# SignalConditioning.net
KiCad netlist of a schematic drawn in Altium Designer
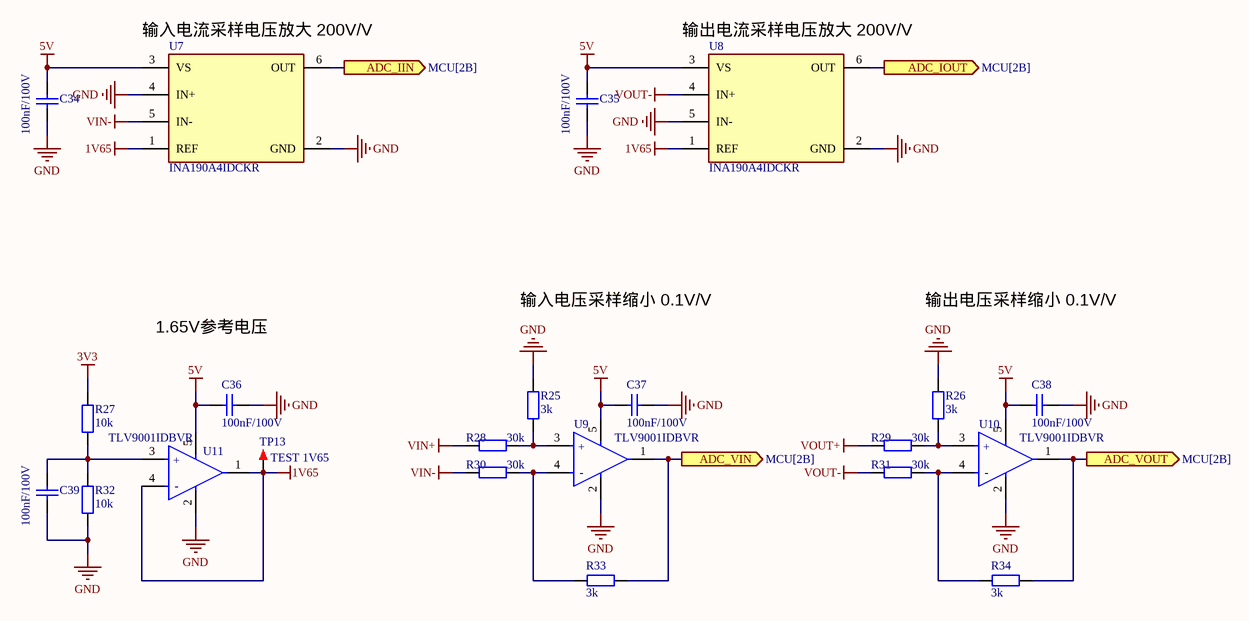
[diagram p0: SignalConditioning.SchDoc]

(export (version "E")
  (design (tool "Eeschema 10.0.6"))
  (components
    (comp (ref "C34")
      (value "100nF/100V")
      (footprint "C0402_L")
      (description "贴片电容")
      (libsource (lib "0.1 - 电阻-电容-电感-晶振-晶体-磁珠-电位器") (part "C"))
    )
    (comp (ref "C35")
      (value "100nF/100V")
      (footprint "C0402_L")
      (description "贴片电容")
      (libsource (lib "0.1 - 电阻-电容-电感-晶振-晶体-磁珠-电位器") (part "C"))
    )
    (comp (ref "C36")
      (value "100nF/100V")
      (footprint "C0402_L")
      (description "贴片电容")
      (libsource (lib "0.1 - 电阻-电容-电感-晶振-晶体-磁珠-电位器") (part "C"))
    )
    (comp (ref "C37")
      (value "100nF/100V")
      (footprint "C0402_L")
      (description "贴片电容")
      (libsource (lib "0.1 - 电阻-电容-电感-晶振-晶体-磁珠-电位器") (part "C"))
    )
    (comp (ref "C38")
      (value "100nF/100V")
      (footprint "C0402_L")
      (description "贴片电容")
      (libsource (lib "0.1 - 电阻-电容-电感-晶振-晶体-磁珠-电位器") (part "C"))
    )
    (comp (ref "C39")
      (value "100nF/100V")
      (footprint "C0402_L")
      (description "贴片电容")
      (libsource (lib "0.1 - 电阻-电容-电感-晶振-晶体-磁珠-电位器") (part "C"))
    )
    (comp (ref "R25")
      (value "3k")
      (footprint "R 0402_L")
      (description "贴片电阻")
      (fields (field (name "版权归属") "源创客"))
      (libsource (lib "源创客") (part "R"))
    )
    (comp (ref "R26")
      (value "3k")
      (footprint "R 0402_L")
      (description "贴片电阻")
      (fields (field (name "版权归属") "源创客"))
      (libsource (lib "源创客") (part "R"))
    )
    (comp (ref "R27")
      (value "10k")
      (footprint "R 0402_L")
      (description "贴片电阻")
      (fields (field (name "版权归属") "源创客"))
      (libsource (lib "源创客") (part "R"))
    )
    (comp (ref "R28")
      (value "30k")
      (footprint "R 0402_L")
      (description "贴片电阻")
      (fields (field (name "版权归属") "源创客"))
      (libsource (lib "源创客") (part "R"))
    )
    (comp (ref "R29")
      (value "30k")
      (footprint "R 0402_L")
      (description "贴片电阻")
      (fields (field (name "版权归属") "源创客"))
      (libsource (lib "源创客") (part "R"))
    )
    (comp (ref "R30")
      (value "30k")
      (footprint "R 0402_L")
      (description "贴片电阻")
      (fields (field (name "版权归属") "源创客"))
      (libsource (lib "源创客") (part "R"))
    )
    (comp (ref "R31")
      (value "30k")
      (footprint "R 0402_L")
      (description "贴片电阻")
      (fields (field (name "版权归属") "源创客"))
      (libsource (lib "源创客") (part "R"))
    )
    (comp (ref "R32")
      (value "10k")
      (footprint "R 0402_L")
      (description "贴片电阻")
      (fields (field (name "版权归属") "源创客"))
      (libsource (lib "源创客") (part "R"))
    )
    (comp (ref "R33")
      (value "3k")
      (footprint "R 0402_L")
      (description "贴片电阻")
      (fields (field (name "版权归属") "源创客"))
      (libsource (lib "源创客") (part "R"))
    )
    (comp (ref "R34")
      (value "3k")
      (footprint "R 0402_L")
      (description "贴片电阻")
      (fields (field (name "版权归属") "源创客"))
      (libsource (lib "源创客") (part "R"))
    )
    (comp (ref "TP13")
      (value "TEST 1V65")
      (footprint "TEST TP1.4_W")
      (description "测试环")
      (libsource (lib "0.5 - 按键-开关-蜂鸣器-保险丝-电池-测试点-Mark点") (part "TEST TP"))
    )
    (comp (ref "U7")
      (value "INA190A4IDCKR")
      (footprint "FP-DCK0006A-IPC_C")
      (description "IC CURR SENSE 1 CIRCUIT SC70-6")
      (libsource (lib "Altium Content Vault") (part "a7b5cee9b6bc60f4871af0ee2c3b109"))
    )
    (comp (ref "U8")
      (value "INA190A4IDCKR")
      (footprint "FP-DCK0006A-IPC_C")
      (description "IC CURR SENSE 1 CIRCUIT SC70-6")
      (libsource (lib "Altium Content Vault") (part "a7b5cee9b6bc60f4871af0ee2c3b109"))
    )
    (comp (ref "U9")
      (value "TLV9001IDBVR")
      (footprint "FP-DBV0005A-IPC_B")
      (description "IC CMOS 1 CIRCUIT SOT23-5")
      (libsource (lib "Altium Content Vault") (part "303ad2592cc7899f5e1082e1d8e7095"))
    )
    (comp (ref "U10")
      (value "TLV9001IDBVR")
      (footprint "FP-DBV0005A-IPC_B")
      (description "IC CMOS 1 CIRCUIT SOT23-5")
      (libsource (lib "Altium Content Vault") (part "303ad2592cc7899f5e1082e1d8e7095"))
    )
    (comp (ref "U11")
      (value "TLV9001IDBVR")
      (footprint "FP-DBV0005A-IPC_B")
      (description "IC CMOS 1 CIRCUIT SOT23-5")
      (libsource (lib "Altium Content Vault") (part "303ad2592cc7899f5e1082e1d8e7095"))
    )
  )
  (nets
    (net (code "1") (name "/ADC_IIN") (class "Default")
      (node (ref "U7") (pin "6") (pinfunction "OUT_6") (pintype "passive"))
    )
    (net (code "2") (name "/ADC_IOUT") (class "Default")
      (node (ref "U8") (pin "6") (pinfunction "OUT_6") (pintype "passive"))
    )
    (net (code "3") (name "/ADC_VIN") (class "Default")
      (node (ref "R33") (pin "1") (pinfunction "1_1") (pintype "passive"))
      (node (ref "U9") (pin "1") (pinfunction "OUT_1") (pintype "passive"))
    )
    (net (code "4") (name "/ADC_VOUT") (class "Default")
      (node (ref "R34") (pin "1") (pinfunction "1_1") (pintype "passive"))
      (node (ref "U10") (pin "1") (pinfunction "OUT_1") (pintype "passive"))
    )
    (net (code "5") (name "1V65") (class "Default")
      (node (ref "TP13") (pin "1") (pinfunction "1_1") (pintype "passive"))
      (node (ref "U11") (pin "1") (pinfunction "OUT_1") (pintype "passive"))
      (node (ref "U11") (pin "4") (pinfunction "IN-_4") (pintype "tri_state"))
      (node (ref "U7") (pin "1") (pinfunction "REF_1") (pintype "passive"))
      (node (ref "U8") (pin "1") (pinfunction "REF_1") (pintype "passive"))
    )
    (net (code "6") (name "3V3") (class "Default")
      (node (ref "R27") (pin "2") (pinfunction "2_2") (pintype "passive"))
    )
    (net (code "7") (name "5V") (class "Default")
      (node (ref "C34") (pin "2") (pinfunction "2_2") (pintype "passive"))
      (node (ref "C35") (pin "2") (pinfunction "2_2") (pintype "passive"))
      (node (ref "C36") (pin "2") (pinfunction "2_2") (pintype "passive"))
      (node (ref "C37") (pin "2") (pinfunction "2_2") (pintype "passive"))
      (node (ref "C38") (pin "2") (pinfunction "2_2") (pintype "passive"))
      (node (ref "U10") (pin "5") (pinfunction "V+_5") (pintype "power_in"))
      (node (ref "U11") (pin "5") (pinfunction "V+_5") (pintype "power_in"))
      (node (ref "U7") (pin "3") (pinfunction "VS_3") (pintype "power_in"))
      (node (ref "U8") (pin "3") (pinfunction "VS_3") (pintype "power_in"))
      (node (ref "U9") (pin "5") (pinfunction "V+_5") (pintype "power_in"))
    )
    (net (code "8") (name "GND") (class "Default")
      (node (ref "C34") (pin "1") (pinfunction "1_1") (pintype "passive"))
      (node (ref "C35") (pin "1") (pinfunction "1_1") (pintype "passive"))
      (node (ref "C36") (pin "1") (pinfunction "1_1") (pintype "passive"))
      (node (ref "C37") (pin "1") (pinfunction "1_1") (pintype "passive"))
      (node (ref "C38") (pin "1") (pinfunction "1_1") (pintype "passive"))
      (node (ref "C39") (pin "1") (pinfunction "1_1") (pintype "passive"))
      (node (ref "R25") (pin "2") (pinfunction "2_2") (pintype "passive"))
      (node (ref "R26") (pin "2") (pinfunction "2_2") (pintype "passive"))
      (node (ref "R32") (pin "1") (pinfunction "1_1") (pintype "passive"))
      (node (ref "U10") (pin "2") (pinfunction "V-_2") (pintype "power_in"))
      (node (ref "U11") (pin "2") (pinfunction "V-_2") (pintype "power_in"))
      (node (ref "U7") (pin "2") (pinfunction "GND_2") (pintype "power_in"))
      (node (ref "U7") (pin "4") (pinfunction "IN+_4") (pintype "tri_state"))
      (node (ref "U8") (pin "2") (pinfunction "GND_2") (pintype "power_in"))
      (node (ref "U8") (pin "5") (pinfunction "IN-_5") (pintype "passive"))
      (node (ref "U9") (pin "2") (pinfunction "V-_2") (pintype "power_in"))
    )
    (net (code "9") (name "Net-(U9-IN+)") (class "Default")
      (node (ref "R25") (pin "1") (pinfunction "1_1") (pintype "passive"))
      (node (ref "R28") (pin "1") (pinfunction "1_1") (pintype "passive"))
      (node (ref "U9") (pin "3") (pinfunction "IN+_3") (pintype "tri_state"))
    )
    (net (code "10") (name "Net-(U9-IN-)") (class "Default")
      (node (ref "R30") (pin "1") (pinfunction "1_1") (pintype "passive"))
      (node (ref "R33") (pin "2") (pinfunction "2_2") (pintype "passive"))
      (node (ref "U9") (pin "4") (pinfunction "IN-_4") (pintype "tri_state"))
    )
    (net (code "11") (name "Net-(U10-IN+)") (class "Default")
      (node (ref "R26") (pin "1") (pinfunction "1_1") (pintype "passive"))
      (node (ref "R29") (pin "1") (pinfunction "1_1") (pintype "passive"))
      (node (ref "U10") (pin "3") (pinfunction "IN+_3") (pintype "tri_state"))
    )
    (net (code "12") (name "Net-(U10-IN-)") (class "Default")
      (node (ref "R31") (pin "1") (pinfunction "1_1") (pintype "passive"))
      (node (ref "R34") (pin "2") (pinfunction "2_2") (pintype "passive"))
      (node (ref "U10") (pin "4") (pinfunction "IN-_4") (pintype "tri_state"))
    )
    (net (code "13") (name "Net-(U11-IN+)") (class "Default")
      (node (ref "C39") (pin "2") (pinfunction "2_2") (pintype "passive"))
      (node (ref "R27") (pin "1") (pinfunction "1_1") (pintype "passive"))
      (node (ref "R32") (pin "2") (pinfunction "2_2") (pintype "passive"))
      (node (ref "U11") (pin "3") (pinfunction "IN+_3") (pintype "tri_state"))
    )
    (net (code "14") (name "VIN+") (class "Default")
      (node (ref "R28") (pin "2") (pinfunction "2_2") (pintype "passive"))
    )
    (net (code "15") (name "VIN-") (class "Default")
      (node (ref "R30") (pin "2") (pinfunction "2_2") (pintype "passive"))
      (node (ref "U7") (pin "5") (pinfunction "IN-_5") (pintype "passive"))
    )
    (net (code "16") (name "VOUT+") (class "Default")
      (node (ref "R29") (pin "2") (pinfunction "2_2") (pintype "passive"))
    )
    (net (code "17") (name "VOUT-") (class "Default")
      (node (ref "R31") (pin "2") (pinfunction "2_2") (pintype "passive"))
      (node (ref "U8") (pin "4") (pinfunction "IN+_4") (pintype "tri_state"))
    )
  )
)
